# twelite.net
KiCad netlist of a schematic drawn in EAGLE
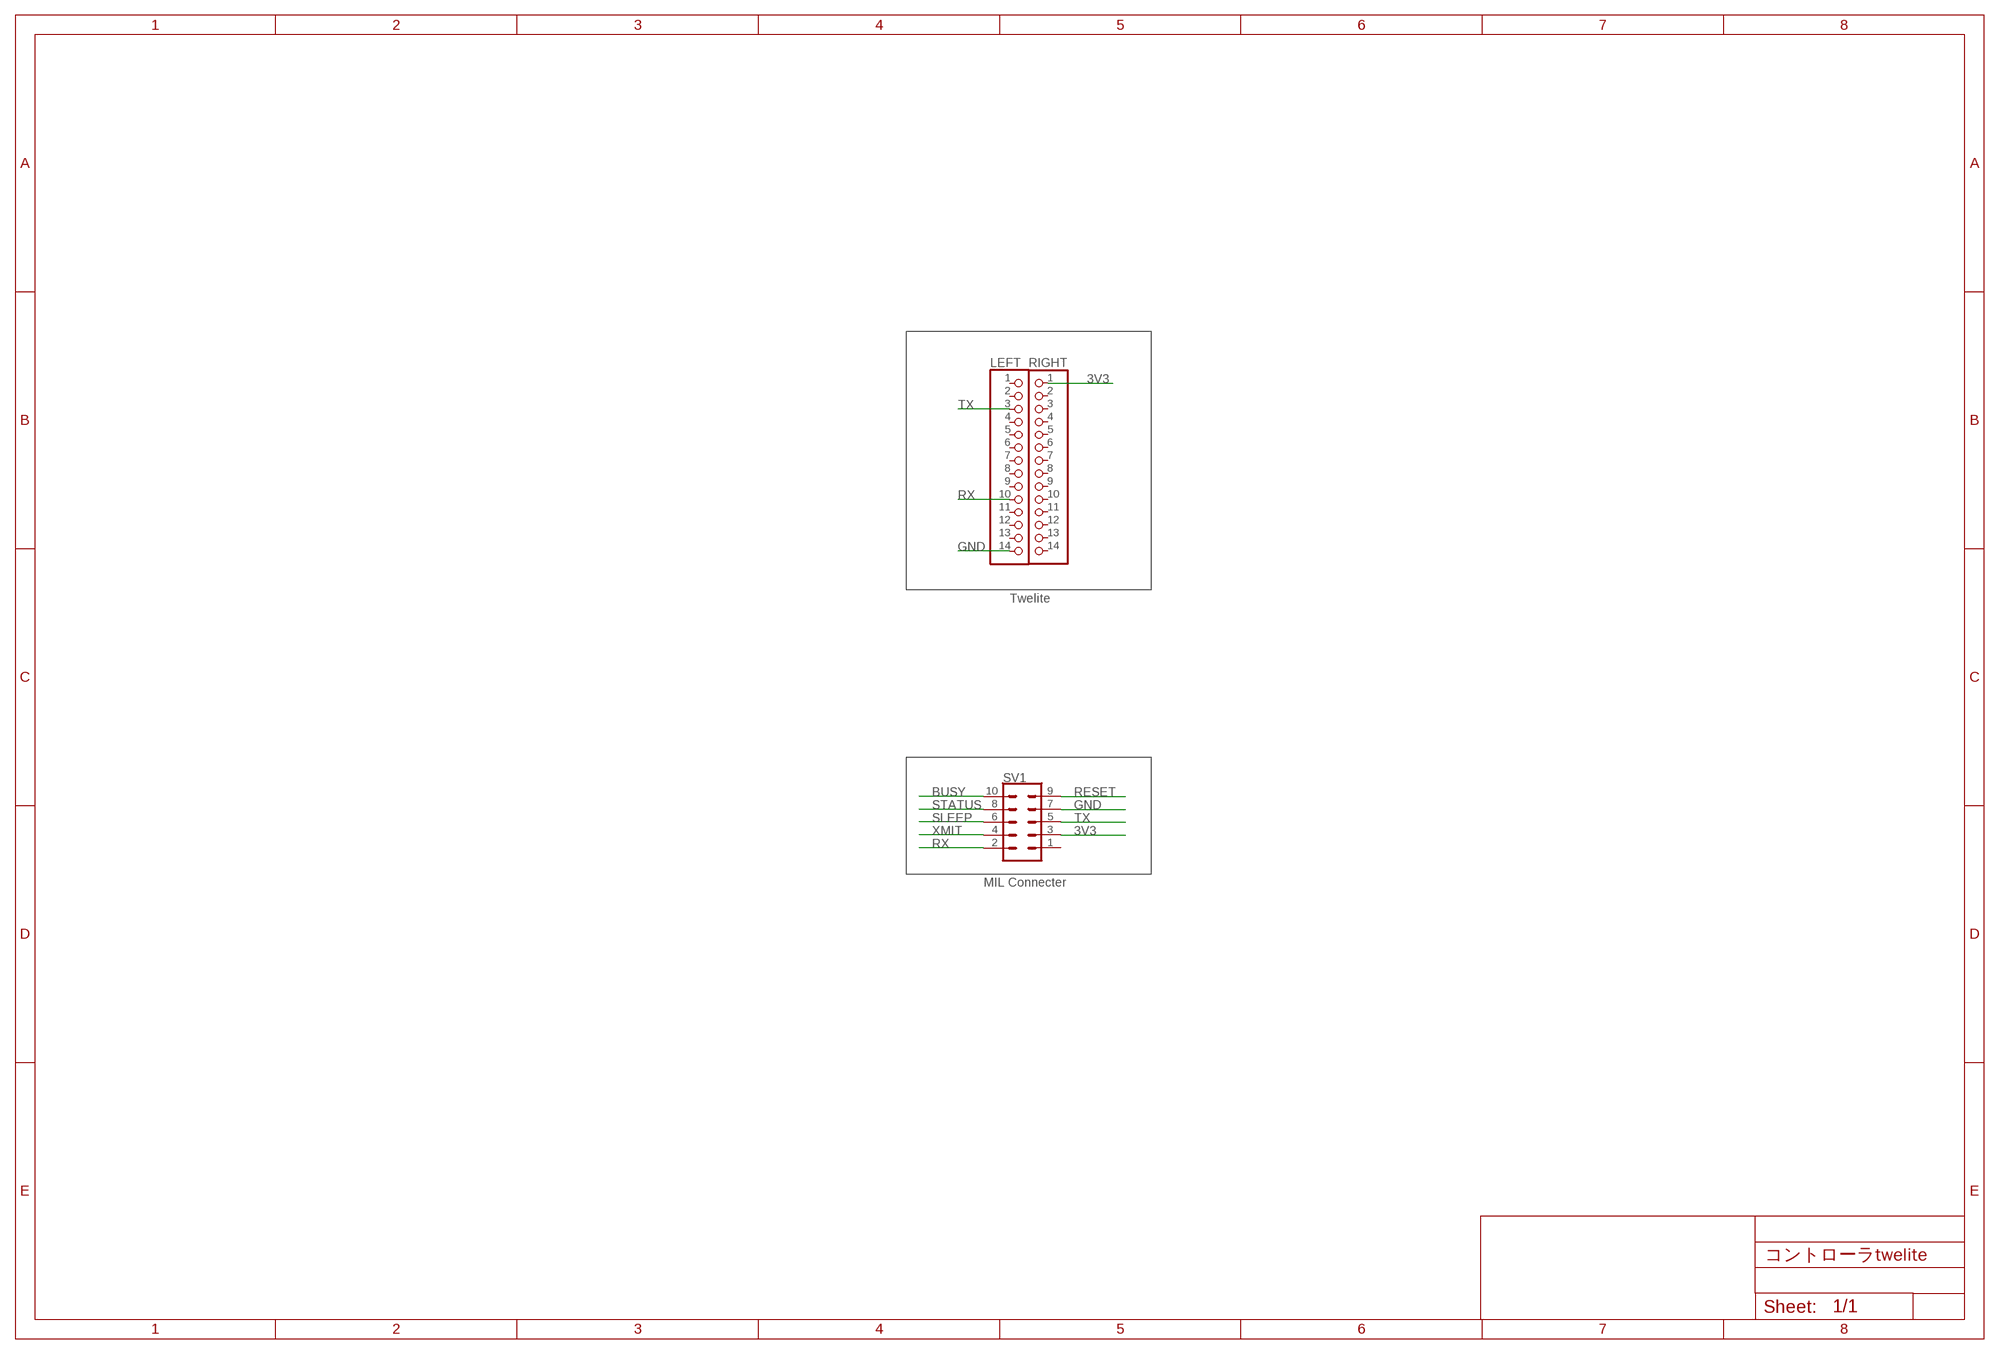
[diagram p0: schematic, sheet 1]

(export (version "E")
  (design (tool "Eeschema 10.0.6"))
  (components
    (comp (ref "LEFT")
      (value "PINHD-1X14")
      (footprint "eagle-import:1X14")
      (libsource (lib "eagle-import") (part "PINHD-1X14"))
    )
    (comp (ref "RIGHT")
      (value "PINHD-1X14")
      (footprint "eagle-import:1X14")
      (libsource (lib "eagle-import") (part "PINHD-1X14"))
    )
    (comp (ref "SV1")
      (value "ML10")
      (footprint "eagle-import:ML10")
      (libsource (lib "eagle-import") (part "ML10"))
    )
  )
  (nets
    (net (code "1") (name "/3V3") (class "Default")
      (node (ref "RIGHT") (pin "1") (pinfunction "1_1") (pintype "passive"))
      (node (ref "SV1") (pin "3") (pinfunction "3_3") (pintype "passive"))
    )
    (net (code "2") (name "/BUSY") (class "Default")
      (node (ref "SV1") (pin "10") (pinfunction "10_10") (pintype "passive"))
    )
    (net (code "3") (name "/GND") (class "Default")
      (node (ref "LEFT") (pin "14") (pinfunction "14_14") (pintype "passive"))
      (node (ref "SV1") (pin "7") (pinfunction "7_7") (pintype "passive"))
    )
    (net (code "4") (name "/RESET") (class "Default")
      (node (ref "SV1") (pin "9") (pinfunction "9_9") (pintype "passive"))
    )
    (net (code "5") (name "/RX") (class "Default")
      (node (ref "LEFT") (pin "10") (pinfunction "10_10") (pintype "passive"))
      (node (ref "SV1") (pin "2") (pinfunction "2_2") (pintype "passive"))
    )
    (net (code "6") (name "/SLEEP") (class "Default")
      (node (ref "SV1") (pin "6") (pinfunction "6_6") (pintype "passive"))
    )
    (net (code "7") (name "/STATUS") (class "Default")
      (node (ref "SV1") (pin "8") (pinfunction "8_8") (pintype "passive"))
    )
    (net (code "8") (name "/TX") (class "Default")
      (node (ref "LEFT") (pin "3") (pinfunction "3_3") (pintype "passive"))
      (node (ref "SV1") (pin "5") (pinfunction "5_5") (pintype "passive"))
    )
    (net (code "9") (name "/XMIT") (class "Default")
      (node (ref "SV1") (pin "4") (pinfunction "4_4") (pintype "passive"))
    )
    (net (code "10") (name "unconnected-(LEFT-Pad1)") (class "Default")
      (node (ref "LEFT") (pin "1") (pinfunction "1_1") (pintype "passive"))
    )
    (net (code "11") (name "unconnected-(LEFT-Pad2)") (class "Default")
      (node (ref "LEFT") (pin "2") (pinfunction "2_2") (pintype "passive"))
    )
    (net (code "12") (name "unconnected-(LEFT-Pad4)") (class "Default")
      (node (ref "LEFT") (pin "4") (pinfunction "4_4") (pintype "passive"))
    )
    (net (code "13") (name "unconnected-(LEFT-Pad5)") (class "Default")
      (node (ref "LEFT") (pin "5") (pinfunction "5_5") (pintype "passive"))
    )
    (net (code "14") (name "unconnected-(LEFT-Pad6)") (class "Default")
      (node (ref "LEFT") (pin "6") (pinfunction "6_6") (pintype "passive"))
    )
    (net (code "15") (name "unconnected-(LEFT-Pad7)") (class "Default")
      (node (ref "LEFT") (pin "7") (pinfunction "7_7") (pintype "passive"))
    )
    (net (code "16") (name "unconnected-(LEFT-Pad8)") (class "Default")
      (node (ref "LEFT") (pin "8") (pinfunction "8_8") (pintype "passive"))
    )
    (net (code "17") (name "unconnected-(LEFT-Pad9)") (class "Default")
      (node (ref "LEFT") (pin "9") (pinfunction "9_9") (pintype "passive"))
    )
    (net (code "18") (name "unconnected-(LEFT-Pad11)") (class "Default")
      (node (ref "LEFT") (pin "11") (pinfunction "11_11") (pintype "passive"))
    )
    (net (code "19") (name "unconnected-(LEFT-Pad12)") (class "Default")
      (node (ref "LEFT") (pin "12") (pinfunction "12_12") (pintype "passive"))
    )
    (net (code "20") (name "unconnected-(LEFT-Pad13)") (class "Default")
      (node (ref "LEFT") (pin "13") (pinfunction "13_13") (pintype "passive"))
    )
    (net (code "21") (name "unconnected-(RIGHT-Pad2)") (class "Default")
      (node (ref "RIGHT") (pin "2") (pinfunction "2_2") (pintype "passive"))
    )
    (net (code "22") (name "unconnected-(RIGHT-Pad3)") (class "Default")
      (node (ref "RIGHT") (pin "3") (pinfunction "3_3") (pintype "passive"))
    )
    (net (code "23") (name "unconnected-(RIGHT-Pad4)") (class "Default")
      (node (ref "RIGHT") (pin "4") (pinfunction "4_4") (pintype "passive"))
    )
    (net (code "24") (name "unconnected-(RIGHT-Pad5)") (class "Default")
      (node (ref "RIGHT") (pin "5") (pinfunction "5_5") (pintype "passive"))
    )
    (net (code "25") (name "unconnected-(RIGHT-Pad6)") (class "Default")
      (node (ref "RIGHT") (pin "6") (pinfunction "6_6") (pintype "passive"))
    )
    (net (code "26") (name "unconnected-(RIGHT-Pad7)") (class "Default")
      (node (ref "RIGHT") (pin "7") (pinfunction "7_7") (pintype "passive"))
    )
    (net (code "27") (name "unconnected-(RIGHT-Pad8)") (class "Default")
      (node (ref "RIGHT") (pin "8") (pinfunction "8_8") (pintype "passive"))
    )
    (net (code "28") (name "unconnected-(RIGHT-Pad9)") (class "Default")
      (node (ref "RIGHT") (pin "9") (pinfunction "9_9") (pintype "passive"))
    )
    (net (code "29") (name "unconnected-(RIGHT-Pad10)") (class "Default")
      (node (ref "RIGHT") (pin "10") (pinfunction "10_10") (pintype "passive"))
    )
    (net (code "30") (name "unconnected-(RIGHT-Pad11)") (class "Default")
      (node (ref "RIGHT") (pin "11") (pinfunction "11_11") (pintype "passive"))
    )
    (net (code "31") (name "unconnected-(RIGHT-Pad12)") (class "Default")
      (node (ref "RIGHT") (pin "12") (pinfunction "12_12") (pintype "passive"))
    )
    (net (code "32") (name "unconnected-(RIGHT-Pad13)") (class "Default")
      (node (ref "RIGHT") (pin "13") (pinfunction "13_13") (pintype "passive"))
    )
    (net (code "33") (name "unconnected-(RIGHT-Pad14)") (class "Default")
      (node (ref "RIGHT") (pin "14") (pinfunction "14_14") (pintype "passive"))
    )
    (net (code "34") (name "unconnected-(SV1-Pad1)") (class "Default")
      (node (ref "SV1") (pin "1") (pinfunction "1_1") (pintype "passive"))
    )
  )
)
